# CON_LCD_TX09D50VM1CAA.net
KiCad netlist of a schematic drawn in Altium Designer
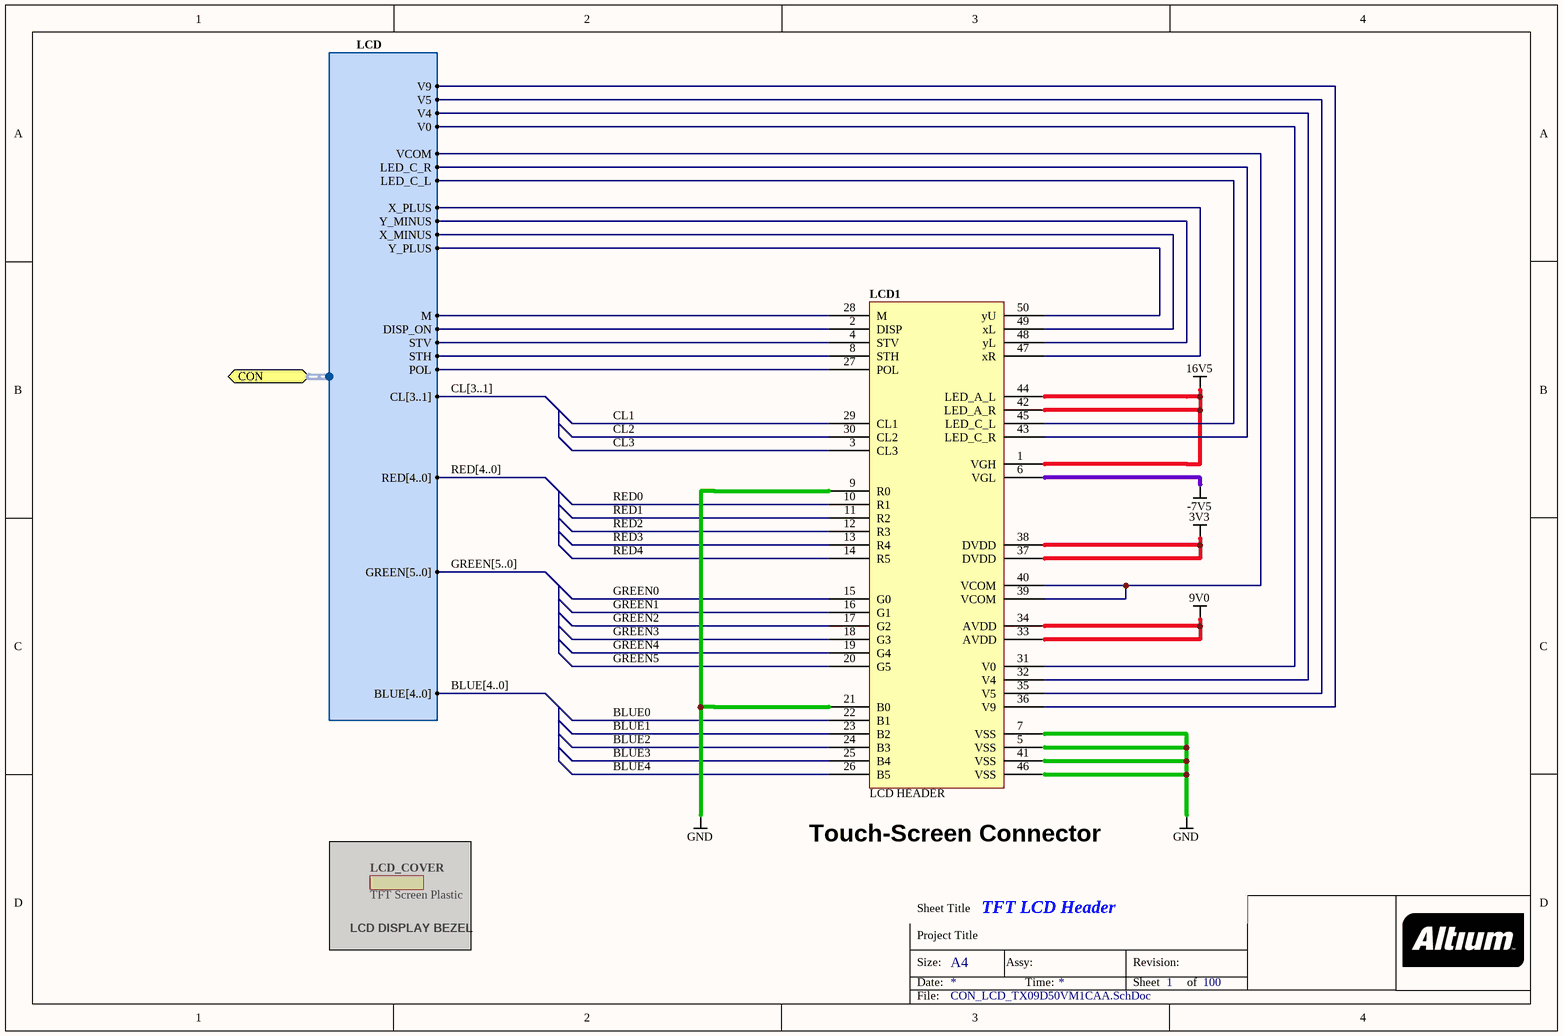
[diagram p0: CON_LCD_TX09D50VM1CAA.SchDoc]

(export (version "E")
  (design (tool "Eeschema 10.0.6"))
  (components
    (comp (ref "LCD1")
      (value "LCD HEADER")
      (footprint "Hitachi_TX09D50VM1CAA")
      (description "Connector, 1 x 50 Pin, 0.5mm Pitch for Hitachi TX09D50VM1CAA TFT")
      (libsource (lib "altium-import") (part "root_0_CON-LCD_"))
    )
    (comp (ref "LCD_COVER")
      (value "TFT Screen Plastic")
      (footprint "NB2 ALTIUM LOGO")
      (libsource (lib "Altium Design Library") (part "Generic No Pins"))
    )
  )
  (nets
    (net (code "2") (name "-7V5") (class "Default")
      (node (ref "LCD1") (pin "6") (pinfunction "VGL_6") (pintype "passive"))
    )
    (net (code "3") (name "/BLUE0") (class "Default")
      (node (ref "LCD1") (pin "22") (pinfunction "B1_22") (pintype "passive"))
    )
    (net (code "4") (name "/BLUE1") (class "Default")
      (node (ref "LCD1") (pin "23") (pinfunction "B2_23") (pintype "passive"))
    )
    (net (code "5") (name "/BLUE2") (class "Default")
      (node (ref "LCD1") (pin "24") (pinfunction "B3_24") (pintype "passive"))
    )
    (net (code "6") (name "/BLUE3") (class "Default")
      (node (ref "LCD1") (pin "25") (pinfunction "B4_25") (pintype "passive"))
    )
    (net (code "7") (name "/BLUE4") (class "Default")
      (node (ref "LCD1") (pin "26") (pinfunction "B5_26") (pintype "passive"))
    )
    (net (code "8") (name "/CL1") (class "Default")
      (node (ref "LCD1") (pin "29") (pinfunction "CL1_29") (pintype "passive"))
    )
    (net (code "9") (name "/CL2") (class "Default")
      (node (ref "LCD1") (pin "30") (pinfunction "CL2_30") (pintype "passive"))
    )
    (net (code "10") (name "/CL3") (class "Default")
      (node (ref "LCD1") (pin "3") (pinfunction "CL3_3") (pintype "passive"))
    )
    (net (code "13") (name "/DISP_ON") (class "Default")
      (node (ref "LCD1") (pin "2") (pinfunction "DISP_2") (pintype "passive"))
    )
    (net (code "14") (name "/GREEN0") (class "Default")
      (node (ref "LCD1") (pin "15") (pinfunction "G0_15") (pintype "passive"))
    )
    (net (code "15") (name "/GREEN1") (class "Default")
      (node (ref "LCD1") (pin "16") (pinfunction "G1_16") (pintype "passive"))
    )
    (net (code "16") (name "/GREEN2") (class "Default")
      (node (ref "LCD1") (pin "17") (pinfunction "G2_17") (pintype "passive"))
    )
    (net (code "17") (name "/GREEN3") (class "Default")
      (node (ref "LCD1") (pin "18") (pinfunction "G3_18") (pintype "passive"))
    )
    (net (code "18") (name "/GREEN4") (class "Default")
      (node (ref "LCD1") (pin "19") (pinfunction "G4_19") (pintype "passive"))
    )
    (net (code "19") (name "/GREEN5") (class "Default")
      (node (ref "LCD1") (pin "20") (pinfunction "G5_20") (pintype "passive"))
    )
    (net (code "21") (name "/LED_C_L") (class "Default")
      (node (ref "LCD1") (pin "45") (pinfunction "LED_C_L_45") (pintype "passive"))
    )
    (net (code "22") (name "/LED_C_R") (class "Default")
      (node (ref "LCD1") (pin "43") (pinfunction "LED_C_R_43") (pintype "passive"))
    )
    (net (code "23") (name "/M") (class "Default")
      (node (ref "LCD1") (pin "28") (pinfunction "M_28") (pintype "passive"))
    )
    (net (code "24") (name "/POL") (class "Default")
      (node (ref "LCD1") (pin "27") (pinfunction "POL_27") (pintype "passive"))
    )
    (net (code "25") (name "/RED0") (class "Default")
      (node (ref "LCD1") (pin "10") (pinfunction "R1_10") (pintype "passive"))
    )
    (net (code "26") (name "/RED1") (class "Default")
      (node (ref "LCD1") (pin "11") (pinfunction "R2_11") (pintype "passive"))
    )
    (net (code "27") (name "/RED2") (class "Default")
      (node (ref "LCD1") (pin "12") (pinfunction "R3_12") (pintype "passive"))
    )
    (net (code "28") (name "/RED3") (class "Default")
      (node (ref "LCD1") (pin "13") (pinfunction "R4_13") (pintype "passive"))
    )
    (net (code "29") (name "/RED4") (class "Default")
      (node (ref "LCD1") (pin "14") (pinfunction "R5_14") (pintype "passive"))
    )
    (net (code "31") (name "/STH") (class "Default")
      (node (ref "LCD1") (pin "8") (pinfunction "STH_8") (pintype "passive"))
    )
    (net (code "32") (name "/STV") (class "Default")
      (node (ref "LCD1") (pin "4") (pinfunction "STV_4") (pintype "passive"))
    )
    (net (code "33") (name "/V0") (class "Default")
      (node (ref "LCD1") (pin "31") (pinfunction "V0_31") (pintype "passive"))
    )
    (net (code "34") (name "/V4") (class "Default")
      (node (ref "LCD1") (pin "32") (pinfunction "V4_32") (pintype "passive"))
    )
    (net (code "35") (name "/V5") (class "Default")
      (node (ref "LCD1") (pin "35") (pinfunction "V5_35") (pintype "passive"))
    )
    (net (code "36") (name "/V9") (class "Default")
      (node (ref "LCD1") (pin "36") (pinfunction "V9_36") (pintype "passive"))
    )
    (net (code "37") (name "/VCOM") (class "Default")
      (node (ref "LCD1") (pin "39") (pinfunction "VCOM_39") (pintype "passive"))
      (node (ref "LCD1") (pin "40") (pinfunction "VCOM_40") (pintype "passive"))
    )
    (net (code "38") (name "/X_MINUS") (class "Default")
      (node (ref "LCD1") (pin "49") (pinfunction "xL_49") (pintype "passive"))
    )
    (net (code "39") (name "/X_PLUS") (class "Default")
      (node (ref "LCD1") (pin "47") (pinfunction "xR_47") (pintype "passive"))
    )
    (net (code "40") (name "/Y_MINUS") (class "Default")
      (node (ref "LCD1") (pin "48") (pinfunction "yL_48") (pintype "passive"))
    )
    (net (code "41") (name "/Y_PLUS") (class "Default")
      (node (ref "LCD1") (pin "50") (pinfunction "yU_50") (pintype "passive"))
    )
    (net (code "43") (name "3V3") (class "Default")
      (node (ref "LCD1") (pin "37") (pinfunction "DVDD_37") (pintype "passive"))
      (node (ref "LCD1") (pin "38") (pinfunction "DVDD_38") (pintype "passive"))
    )
    (net (code "44") (name "9V0") (class "Default")
      (node (ref "LCD1") (pin "33") (pinfunction "AVDD_33") (pintype "passive"))
      (node (ref "LCD1") (pin "34") (pinfunction "AVDD_34") (pintype "passive"))
    )
    (net (code "45") (name "16V5") (class "Default")
      (node (ref "LCD1") (pin "1") (pinfunction "VGH_1") (pintype "passive"))
      (node (ref "LCD1") (pin "42") (pinfunction "LED_A_R_42") (pintype "passive"))
      (node (ref "LCD1") (pin "44") (pinfunction "LED_A_L_44") (pintype "passive"))
    )
    (net (code "46") (name "GND") (class "Default")
      (node (ref "LCD1") (pin "21") (pinfunction "B0_21") (pintype "passive"))
      (node (ref "LCD1") (pin "41") (pinfunction "VSS_41") (pintype "passive"))
      (node (ref "LCD1") (pin "46") (pinfunction "VSS_46") (pintype "passive"))
      (node (ref "LCD1") (pin "5") (pinfunction "VSS_5") (pintype "passive"))
      (node (ref "LCD1") (pin "7") (pinfunction "VSS_7") (pintype "passive"))
      (node (ref "LCD1") (pin "9") (pinfunction "R0_9") (pintype "passive"))
    )
  )
)
